# AlexRJ12-14.net
KiCad netlist of a schematic drawn in EAGLE
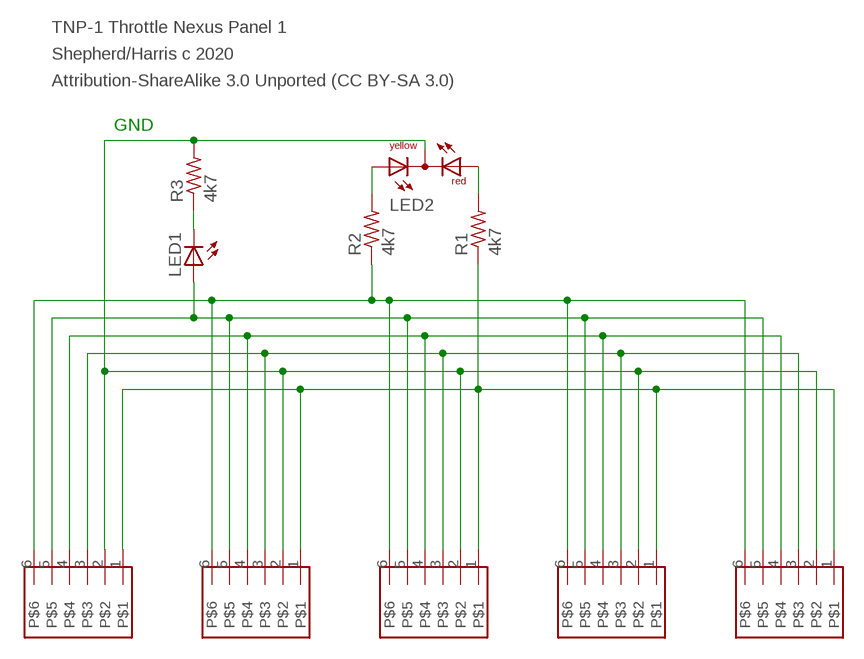
[diagram p0: schematic, sheet 1]

(export (version "E")
  (design (tool "Eeschema 10.0.6"))
  (components
    (comp (ref "LED1")
      (value "LED5MM")
      (footprint "eagle-import:LED5MM")
      (libsource (lib "eagle-import") (part "LED5MM"))
    )
    (comp (ref "LED2")
      (value "DUOLED-RY-C")
      (footprint "eagle-import:DUOLED-C-5MM")
      (libsource (lib "eagle-import") (part "DUOLED-RY-C"))
    )
    (comp (ref "R1")
      (value "4k7")
      (footprint "eagle-import:0207_7")
      (libsource (lib "eagle-import") (part "R-US_0207/7"))
    )
    (comp (ref "R2")
      (value "4k7")
      (footprint "eagle-import:0207_7")
      (libsource (lib "eagle-import") (part "R-US_0207/7"))
    )
    (comp (ref "R3")
      (value "4k7")
      (footprint "eagle-import:0207_7")
      (libsource (lib "eagle-import") (part "R-US_0207/7"))
    )
    (comp (ref "U$1")
      (value "RJ12-6")
      (footprint "eagle-import:RJ12-6")
      (libsource (lib "eagle-import") (part "RJ12-6"))
    )
    (comp (ref "U$2")
      (value "RJ12-6")
      (footprint "eagle-import:RJ12-6")
      (libsource (lib "eagle-import") (part "RJ12-6"))
    )
    (comp (ref "U$3")
      (value "RJ12-6")
      (footprint "eagle-import:RJ12-6")
      (libsource (lib "eagle-import") (part "RJ12-6"))
    )
    (comp (ref "U$4")
      (value "RJ12-6")
      (footprint "eagle-import:RJ12-6")
      (libsource (lib "eagle-import") (part "RJ12-6"))
    )
    (comp (ref "U$5")
      (value "RJ12-6")
      (footprint "eagle-import:RJ12-6")
      (libsource (lib "eagle-import") (part "RJ12-6"))
    )
  )
  (nets
    (net (code "1") (name "Net-(LED1-C)") (class "Default")
      (node (ref "LED1") (pin "K") (pinfunction "C_K") (pintype "passive"))
      (node (ref "R3") (pin "1") (pinfunction "1_1") (pintype "passive"))
    )
    (net (code "2") (name "Net-(LED2-AY)") (class "Default")
      (node (ref "LED2") (pin "AX") (pinfunction "AY_AX") (pintype "passive"))
      (node (ref "R2") (pin "2") (pinfunction "2_2") (pintype "passive"))
    )
    (net (code "3") (name "Net-(LED2-PadAR)") (class "Default")
      (node (ref "LED2") (pin "AR") (pinfunction "AR_AR") (pintype "passive"))
      (node (ref "R1") (pin "2") (pinfunction "2_2") (pintype "passive"))
    )
    (net (code "4") (name "Net-(U$1-P$1)") (class "Default")
      (node (ref "R1") (pin "1") (pinfunction "1_1") (pintype "passive"))
      (node (ref "U$1") (pin "1") (pinfunction "P$1_1") (pintype "bidirectional"))
      (node (ref "U$2") (pin "1") (pinfunction "P$1_1") (pintype "bidirectional"))
      (node (ref "U$3") (pin "1") (pinfunction "P$1_1") (pintype "bidirectional"))
      (node (ref "U$4") (pin "1") (pinfunction "P$1_1") (pintype "bidirectional"))
      (node (ref "U$5") (pin "1") (pinfunction "P$1_1") (pintype "bidirectional"))
    )
    (net (code "5") (name "Net-(U$1-P$2)") (class "Default")
      (node (ref "LED2") (pin "C") (pinfunction "C_C") (pintype "passive"))
      (node (ref "R3") (pin "2") (pinfunction "2_2") (pintype "passive"))
      (node (ref "U$1") (pin "2") (pinfunction "P$2_2") (pintype "bidirectional"))
      (node (ref "U$2") (pin "2") (pinfunction "P$2_2") (pintype "bidirectional"))
      (node (ref "U$3") (pin "2") (pinfunction "P$2_2") (pintype "bidirectional"))
      (node (ref "U$4") (pin "2") (pinfunction "P$2_2") (pintype "bidirectional"))
      (node (ref "U$5") (pin "2") (pinfunction "P$2_2") (pintype "bidirectional"))
    )
    (net (code "6") (name "Net-(U$1-P$3)") (class "Default")
      (node (ref "U$1") (pin "3") (pinfunction "P$3_3") (pintype "bidirectional"))
      (node (ref "U$2") (pin "3") (pinfunction "P$3_3") (pintype "bidirectional"))
      (node (ref "U$3") (pin "3") (pinfunction "P$3_3") (pintype "bidirectional"))
      (node (ref "U$4") (pin "3") (pinfunction "P$3_3") (pintype "bidirectional"))
      (node (ref "U$5") (pin "3") (pinfunction "P$3_3") (pintype "bidirectional"))
    )
    (net (code "7") (name "Net-(U$1-P$4)") (class "Default")
      (node (ref "U$1") (pin "4") (pinfunction "P$4_4") (pintype "bidirectional"))
      (node (ref "U$2") (pin "4") (pinfunction "P$4_4") (pintype "bidirectional"))
      (node (ref "U$3") (pin "4") (pinfunction "P$4_4") (pintype "bidirectional"))
      (node (ref "U$4") (pin "4") (pinfunction "P$4_4") (pintype "bidirectional"))
      (node (ref "U$5") (pin "4") (pinfunction "P$4_4") (pintype "bidirectional"))
    )
    (net (code "8") (name "Net-(U$1-P$5)") (class "Default")
      (node (ref "LED1") (pin "A") (pinfunction "A_A") (pintype "passive"))
      (node (ref "U$1") (pin "5") (pinfunction "P$5_5") (pintype "bidirectional"))
      (node (ref "U$2") (pin "5") (pinfunction "P$5_5") (pintype "bidirectional"))
      (node (ref "U$3") (pin "5") (pinfunction "P$5_5") (pintype "bidirectional"))
      (node (ref "U$4") (pin "5") (pinfunction "P$5_5") (pintype "bidirectional"))
      (node (ref "U$5") (pin "5") (pinfunction "P$5_5") (pintype "bidirectional"))
    )
    (net (code "9") (name "Net-(U$1-P$6)") (class "Default")
      (node (ref "R2") (pin "1") (pinfunction "1_1") (pintype "passive"))
      (node (ref "U$1") (pin "6") (pinfunction "P$6_6") (pintype "bidirectional"))
      (node (ref "U$2") (pin "6") (pinfunction "P$6_6") (pintype "bidirectional"))
      (node (ref "U$3") (pin "6") (pinfunction "P$6_6") (pintype "bidirectional"))
      (node (ref "U$4") (pin "6") (pinfunction "P$6_6") (pintype "bidirectional"))
      (node (ref "U$5") (pin "6") (pinfunction "P$6_6") (pintype "bidirectional"))
    )
  )
)
